# Pressure_Measurement.net
KiCad netlist of a schematic drawn in Altium Designer
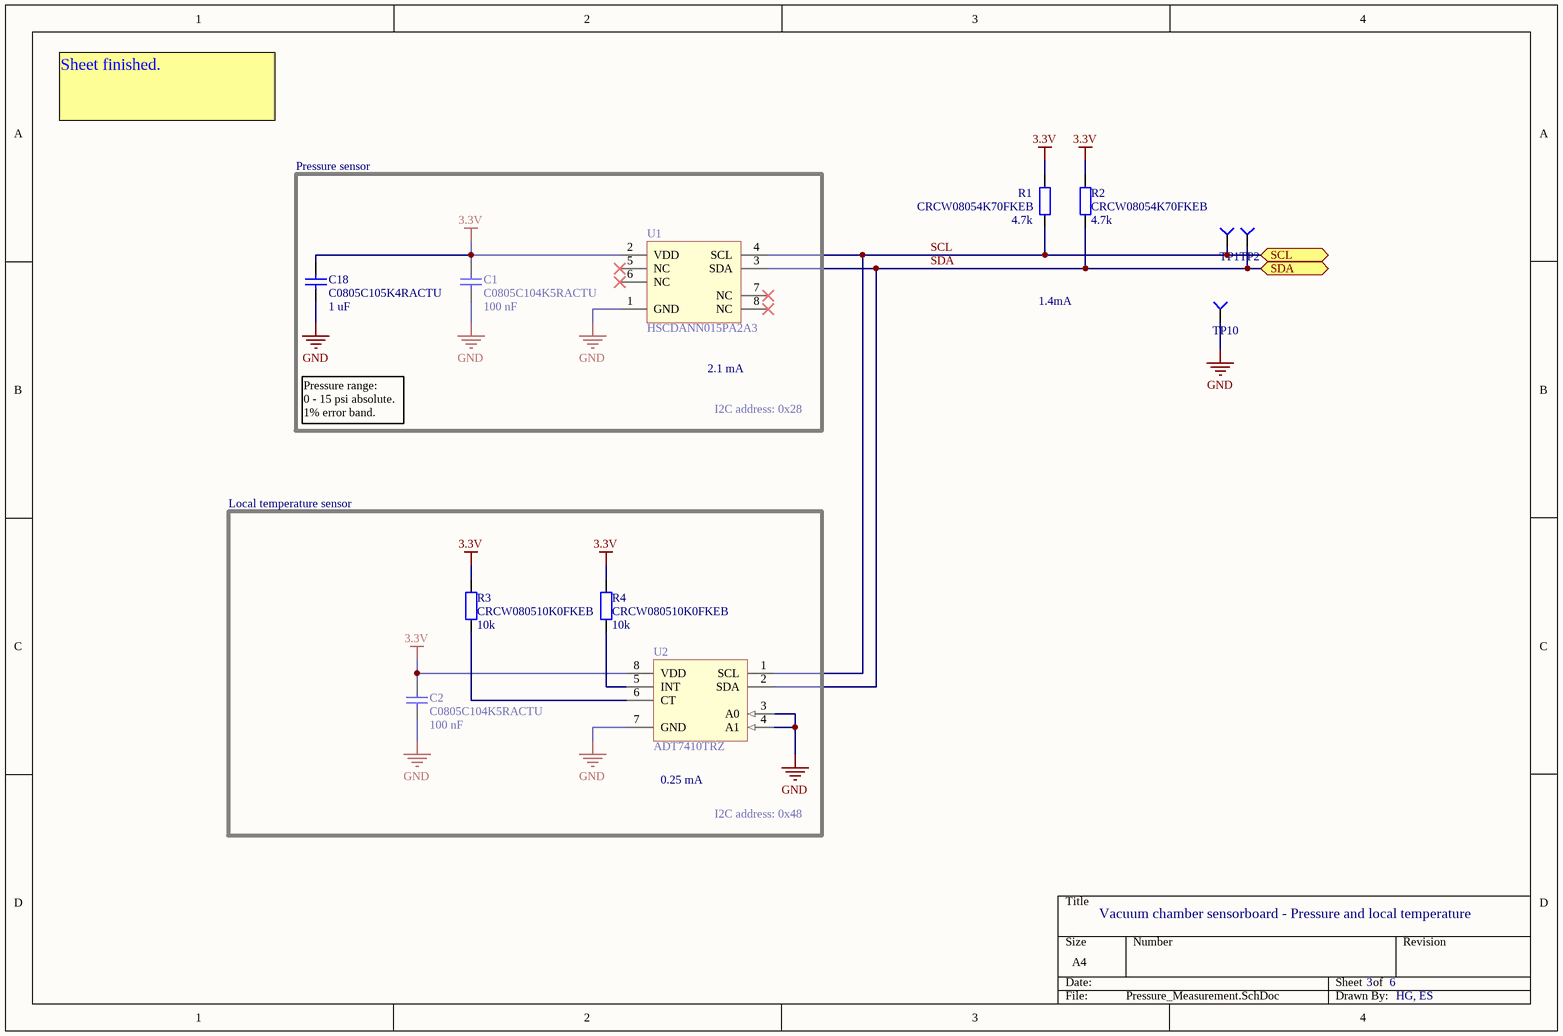
[diagram p0: Pressure_Measurement.SchDoc]

(export (version "E")
  (design (tool "Eeschema 10.0.6"))
  (components
    (comp (ref "C1")
      (value "C0805C104K5RACTU")
      (footprint "Cap Kemet 0805")
      (description "Ceramic capacitor, X7R, 10%, 50V")
      (fields (field (name "MANUFACTURER") "Kemet") (field (name "ALTIUM_VALUE") "100 nF"))
      (libsource (lib "EITlib") (part "C0805C104K5RACTU"))
    )
    (comp (ref "C2")
      (value "C0805C104K5RACTU")
      (footprint "Cap Kemet 0805")
      (description "Ceramic capacitor, X7R, 10%, 50V")
      (fields (field (name "MANUFACTURER") "Kemet") (field (name "ALTIUM_VALUE") "100 nF"))
      (libsource (lib "EITlib") (part "C0805C104K5RACTU"))
    )
    (comp (ref "C18")
      (value "C0805C105K4RACTU")
      (footprint "Cap Kemet 0805")
      (description "Ceramic capacitor, X7R, 10%, 16V")
      (fields (field (name "MANUFACTURER") "Kemet") (field (name "ALTIUM_VALUE") "1 uF"))
      (libsource (lib "EITlib") (part "C0805C105K4RACTU"))
    )
    (comp (ref "R1")
      (value "CRCW08054K70FKEB")
      (footprint "Res Vishay0805")
      (description "Thick film resistor, 1%, 125mW")
      (fields (field (name "MANUFACTURER") "Vishay") (field (name "ALTIUM_VALUE") "4.7k"))
      (libsource (lib "EITlib") (part "CRCW08054K70FKEB"))
    )
    (comp (ref "R2")
      (value "CRCW08054K70FKEB")
      (footprint "Res Vishay0805")
      (description "Thick film resistor, 1%, 125mW")
      (fields (field (name "MANUFACTURER") "Vishay") (field (name "ALTIUM_VALUE") "4.7k"))
      (libsource (lib "EITlib") (part "CRCW08054K70FKEB"))
    )
    (comp (ref "R3")
      (value "CRCW080510K0FKEB")
      (footprint "Res Vishay0805")
      (description "Thick film resistor, 1%, 125mW")
      (fields (field (name "MANUFACTURER") "Vishay") (field (name "ALTIUM_VALUE") "10k"))
      (libsource (lib "EITlib") (part "CRCW080510K0FKEB"))
    )
    (comp (ref "R4")
      (value "CRCW080510K0FKEB")
      (footprint "Res Vishay0805")
      (description "Thick film resistor, 1%, 125mW")
      (fields (field (name "MANUFACTURER") "Vishay") (field (name "ALTIUM_VALUE") "10k"))
      (libsource (lib "EITlib") (part "CRCW080510K0FKEB"))
    )
    (comp (ref "TP1")
      (value "Test_point")
      (footprint "Testpoint")
      (libsource (lib "EITlib") (part "Test_point"))
    )
    (comp (ref "TP2")
      (value "Test_point")
      (footprint "Testpoint")
      (libsource (lib "EITlib") (part "Test_point"))
    )
    (comp (ref "TP10")
      (value "Test_point")
      (footprint "Testpoint")
      (libsource (lib "EITlib") (part "Test_point"))
    )
    (comp (ref "U1")
      (value "HSCDANN015PA2A3")
      (footprint "HSCDANN015PA2A3 Pressure sensor")
      (description "Absolute pressure sensor, I2C output")
      (libsource (lib "EITlib") (part "HSCDANN015PA2A3"))
    )
    (comp (ref "U2")
      (value "ADT7410TRZ")
      (footprint "ADT7410")
      (description "Temperature sensor, I2C output")
      (libsource (lib "EITlib") (part "ADT7410TRZ"))
    )
  )
  (nets
    (net (code "1") (name "/SCL") (class "Default")
      (node (ref "R1") (pin "1") (pinfunction "1_1") (pintype "passive"))
      (node (ref "TP1") (pin "0") (pinfunction "0_0") (pintype "passive"))
      (node (ref "U1") (pin "4") (pinfunction "SCL_4") (pintype "open_collector"))
      (node (ref "U2") (pin "1") (pinfunction "SCL_1") (pintype "open_collector"))
    )
    (net (code "2") (name "/SDA") (class "Default")
      (node (ref "R2") (pin "1") (pinfunction "1_1") (pintype "passive"))
      (node (ref "TP2") (pin "0") (pinfunction "0_0") (pintype "passive"))
      (node (ref "U1") (pin "3") (pinfunction "SDA_3") (pintype "open_collector"))
      (node (ref "U2") (pin "2") (pinfunction "SDA_2") (pintype "open_collector"))
    )
    (net (code "3") (name "3.3V") (class "Default")
      (node (ref "C1") (pin "2") (pinfunction "2_2") (pintype "passive"))
      (node (ref "C18") (pin "2") (pinfunction "2_2") (pintype "passive"))
      (node (ref "C2") (pin "2") (pinfunction "2_2") (pintype "passive"))
      (node (ref "R1") (pin "2") (pinfunction "2_2") (pintype "passive"))
      (node (ref "R2") (pin "2") (pinfunction "2_2") (pintype "passive"))
      (node (ref "R3") (pin "2") (pinfunction "2_2") (pintype "passive"))
      (node (ref "R4") (pin "2") (pinfunction "2_2") (pintype "passive"))
      (node (ref "U1") (pin "2") (pinfunction "VDD_2") (pintype "power_in"))
      (node (ref "U2") (pin "8") (pinfunction "VDD_8") (pintype "power_in"))
    )
    (net (code "4") (name "GND") (class "Default")
      (node (ref "C1") (pin "1") (pinfunction "1_1") (pintype "passive"))
      (node (ref "C18") (pin "1") (pinfunction "1_1") (pintype "passive"))
      (node (ref "C2") (pin "1") (pinfunction "1_1") (pintype "passive"))
      (node (ref "TP10") (pin "0") (pinfunction "0_0") (pintype "passive"))
      (node (ref "U1") (pin "1") (pinfunction "GND_1") (pintype "power_in"))
      (node (ref "U2") (pin "3") (pinfunction "A0_3") (pintype "input"))
      (node (ref "U2") (pin "4") (pinfunction "A1_4") (pintype "input"))
      (node (ref "U2") (pin "7") (pinfunction "GND_7") (pintype "power_in"))
    )
    (net (code "5") (name "Net-(U2-CT)") (class "Default")
      (node (ref "R3") (pin "1") (pinfunction "1_1") (pintype "passive"))
      (node (ref "U2") (pin "6") (pinfunction "CT_6") (pintype "open_collector"))
    )
    (net (code "6") (name "Net-(U2-INT)") (class "Default")
      (node (ref "R4") (pin "1") (pinfunction "1_1") (pintype "passive"))
      (node (ref "U2") (pin "5") (pinfunction "INT_5") (pintype "open_collector"))
    )
    (net (code "7") (name "unconnected-(U1-NC-Pad5)") (class "Default")
      (node (ref "U1") (pin "5") (pinfunction "NC_5") (pintype "passive+no_connect"))
    )
    (net (code "8") (name "unconnected-(U1-NC-Pad6)") (class "Default")
      (node (ref "U1") (pin "6") (pinfunction "NC_6") (pintype "passive+no_connect"))
    )
    (net (code "9") (name "unconnected-(U1-NC-Pad7)") (class "Default")
      (node (ref "U1") (pin "7") (pinfunction "NC_7") (pintype "passive+no_connect"))
    )
    (net (code "10") (name "unconnected-(U1-NC-Pad8)") (class "Default")
      (node (ref "U1") (pin "8") (pinfunction "NC_8") (pintype "passive+no_connect"))
    )
  )
)
